# Modem.net
KiCad netlist of a schematic drawn in Altium Designer
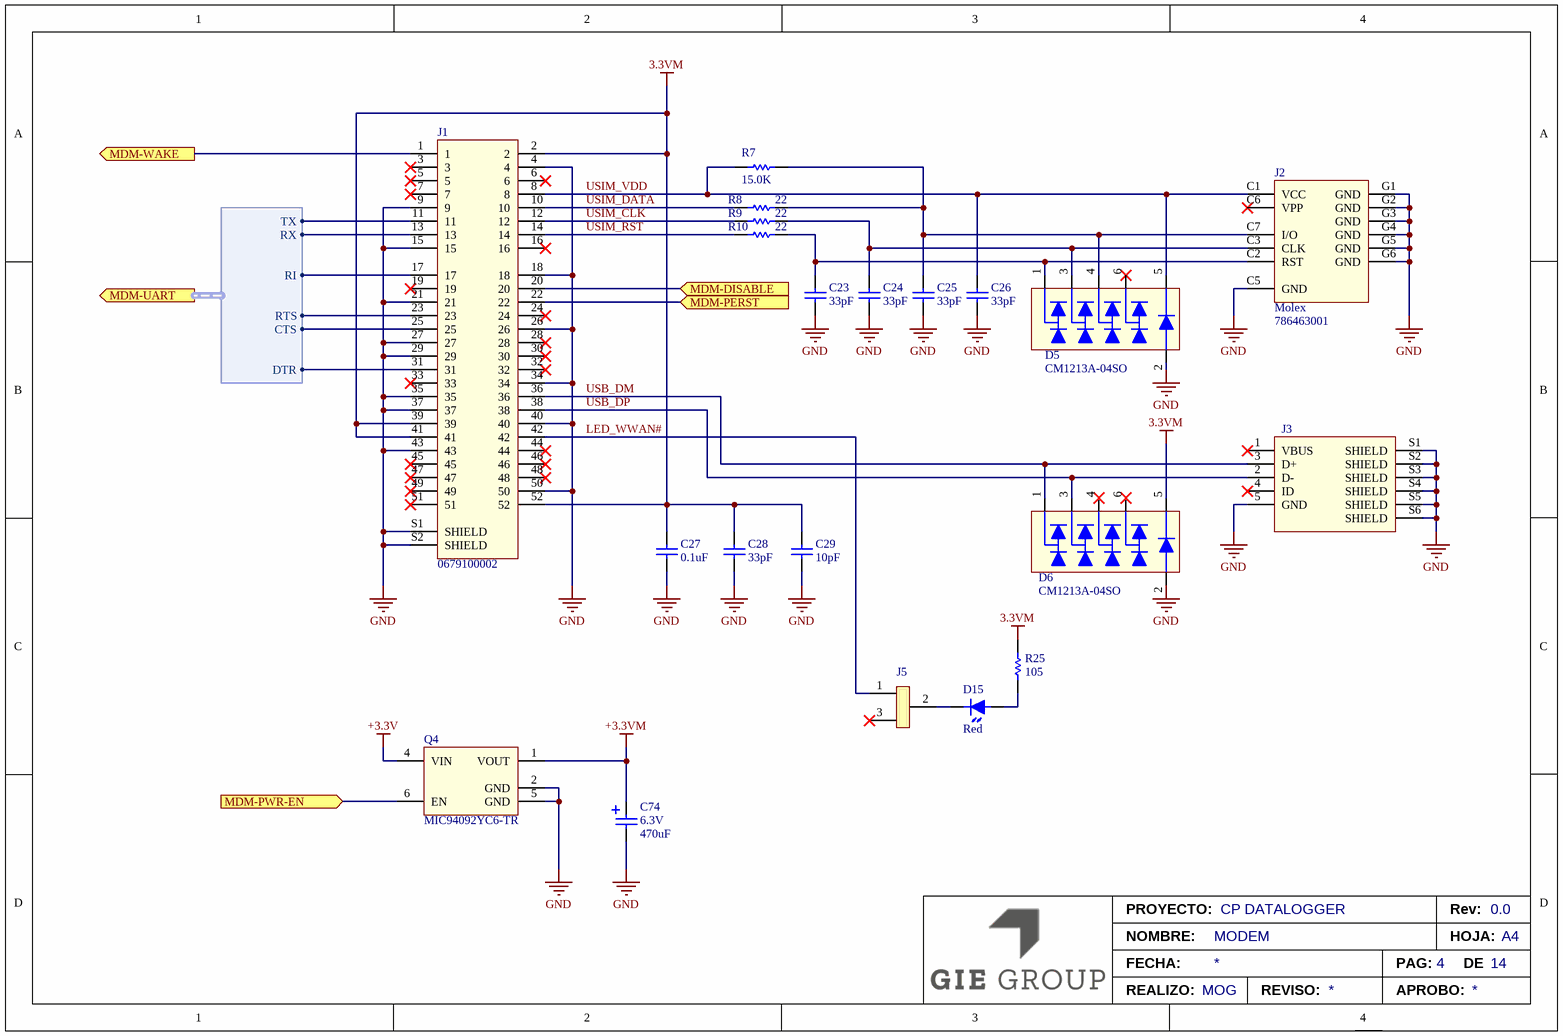
[diagram p0: Modem.SchDoc]

(export (version "E")
  (design (tool "Eeschema 10.0.6"))
  (components
    (comp (ref "C23")
      (value "33pF")
      (footprint "CAP-0603")
      (description "CAP CER 33 pF 25V C0G 0603")
      (fields (field (name "PARTNUMBER") "C0603C330F3GAC7867") (field (name "MANUFACTURER") "Kemet"))
      (libsource (lib "Kemet") (part "C0603C330F3GAC7867"))
    )
    (comp (ref "C24")
      (value "33pF")
      (footprint "CAP-0603")
      (description "CAP CER 33 pF 25V C0G 0603")
      (fields (field (name "PARTNUMBER") "C0603C330F3GAC7867") (field (name "MANUFACTURER") "Kemet"))
      (libsource (lib "Kemet") (part "C0603C330F3GAC7867"))
    )
    (comp (ref "C25")
      (value "33pF")
      (footprint "CAP-0603")
      (description "CAP CER 33 pF 25V C0G 0603")
      (fields (field (name "PARTNUMBER") "C0603C330F3GAC7867") (field (name "MANUFACTURER") "Kemet"))
      (libsource (lib "Kemet") (part "C0603C330F3GAC7867"))
    )
    (comp (ref "C26")
      (value "33pF")
      (footprint "CAP-0603")
      (description "CAP CER 33 pF 25V C0G 0603")
      (fields (field (name "PARTNUMBER") "C0603C330F3GAC7867") (field (name "MANUFACTURER") "Kemet"))
      (libsource (lib "Kemet") (part "C0603C330F3GAC7867"))
    )
    (comp (ref "C27")
      (value "0.1uF")
      (footprint "CAP-0603")
      (description "CAP CER 0.1uF 50V X7R 0603")
      (fields (field (name "PARTNUMBER") "C0603C104K5RACAUTO") (field (name "MANUFACTURER") "Kemet"))
      (libsource (lib "Kemet") (part "C0603C104K5RACAUTO"))
    )
    (comp (ref "C28")
      (value "33pF")
      (footprint "CAP-0603")
      (description "CAP CER 33 pF 25V C0G 0603")
      (fields (field (name "PARTNUMBER") "C0603C330F3GAC7867") (field (name "MANUFACTURER") "Kemet"))
      (libsource (lib "Kemet") (part "C0603C330F3GAC7867"))
    )
    (comp (ref "C29")
      (value "10pF")
      (footprint "CAP-0603")
      (description "CAP CER 10 pF 25V C0G 0603")
      (fields (field (name "PARTNUMBER") "C0603C100K3GAC7867") (field (name "MANUFACTURER") "Kemet"))
      (libsource (lib "Kemet") (part "C0603C100K3GAC7867"))
    )
    (comp (ref "C74")
      (value "470uF")
      (footprint "CAP_ALUM_SIZE_F")
      (description "CAP ALUM 470UF 20% 6.3V SMD")
      (fields
        (field (name "MANUFACTURER") "Panasonic")
        (field (name "VOLTAGE") "6.3V")
        (field (name "Comment") "EEE-FK0J471P")
      )
      (libsource (lib "Panasonic") (part "EEE-FK0J471P"))
    )
    (comp (ref "D5")
      (value "CM1213A-04SO")
      (footprint "TSSOP6")
      (description "TVS DIODE 3.3VWM 10VC 4CH SC74")
      (fields (field (name "MANUFACTURER") "OnSemiconductor") (field (name "PARTNUMBER") "CM1213A-04SO"))
      (libsource (lib "OnSemiconductors") (part "CM1213A-04SO"))
    )
    (comp (ref "D6")
      (value "CM1213A-04SO")
      (footprint "TSSOP6")
      (description "TVS DIODE 3.3VWM 10VC 4CH SC74")
      (fields (field (name "MANUFACTURER") "OnSemiconductor") (field (name "PARTNUMBER") "CM1213A-04SO"))
      (libsource (lib "OnSemiconductors") (part "CM1213A-04SO"))
    )
    (comp (ref "D15")
      (value "LTST-C170KRKT")
      (footprint "0805 - LED")
      (description "LED RED CLEAR 0805 SMD")
      (fields (field (name "MANUFACTURER") "Lite-On Inc") (field (name "COLOR") "Red"))
      (libsource (lib "LiteOn") (part "LTST-C170KRKT"))
    )
    (comp (ref "J1")
      (value "0679100002")
      (footprint "MOLEX-679100002")
      (description "Connector Mini PCI Express 52POS - Quectel modem")
      (fields (field (name "MANUFACTURER") "Molex"))
      (libsource (lib "Molex") (part "Molex 0679100002"))
    )
    (comp (ref "J2")
      (value "786463001")
      (footprint "MOLEX-786463001")
      (description "6 Position Card Connector Micro SIM Surface Mount, Right Angle Gold")
      (fields (field (name "MANUFACTURER") "Molex") (field (name "PARTNUMBER") "786463001"))
      (libsource (lib "Molex") (part "786463001"))
    )
    (comp (ref "J3")
      (value "473460001")
      (footprint "MOLEX-473460001")
      (description "USB Connectors MICRO USB B RECPT BTTM MOUNT ASSY")
      (fields (field (name "MANUFACTURER") "Molex"))
      (libsource (lib "Molex") (part "473460001"))
    )
    (comp (ref "J5")
      (value "PRPC003SAAN-RC")
      (footprint "PIN3")
      (description "CONN HEADER .100\" SNGL STR 3POS")
      (fields (field (name "MANUFACTURER") "Sullins Connector Solutions"))
      (libsource (lib "Sullins") (part "PRPC003SAAN-RC"))
    )
    (comp (ref "Q4")
      (value "MIC94092YC6-TR")
      (footprint "TSSOP6")
      (fields (field (name "MANUFACTURER") "Microchip") (field (name "PARTNUMBER") "MIC94092YC6-TR"))
      (libsource (lib "Microchip") (part "MIC94092YC6-TR"))
    )
    (comp (ref "R7")
      (value "15.0K")
      (footprint "RES-0603")
      (description "RES SMD 15.0K OHM 1% 1/10W 0603")
      (fields (field (name "TOLERANCE") "1%") (field (name "MANUFACTURER") "Yageo"))
      (libsource (lib "Yageo") (part "RC0603FR-0715KL"))
    )
    (comp (ref "R8")
      (value "22")
      (footprint "RES-0603")
      (description "RES SMD 22 OHM 1% 1/10W 0603")
      (fields (field (name "TOLERANCE") "1%") (field (name "MANUFACTURER") "Yageo"))
      (libsource (lib "Yageo") (part "RC0603FR-0722RL"))
    )
    (comp (ref "R9")
      (value "22")
      (footprint "RES-0603")
      (description "RES SMD 22 OHM 1% 1/10W 0603")
      (fields (field (name "TOLERANCE") "1%") (field (name "MANUFACTURER") "Yageo"))
      (libsource (lib "Yageo") (part "RC0603FR-0722RL"))
    )
    (comp (ref "R10")
      (value "22")
      (footprint "RES-0603")
      (description "RES SMD 22 OHM 1% 1/10W 0603")
      (fields (field (name "TOLERANCE") "1%") (field (name "MANUFACTURER") "Yageo"))
      (libsource (lib "Yageo") (part "RC0603FR-0722RL"))
    )
    (comp (ref "R25")
      (value "105")
      (footprint "RES-0603")
      (description "RES SMD 105 OHM 1% 1/8W 0805")
      (fields (field (name "TOLERANCE") "1%") (field (name "MANUFACTURER") "Yageo"))
      (libsource (lib "Yageo") (part "RC0805FR-07105RL"))
    )
  )
  (nets
    (net (code "2") (name "+3.3V") (class "Default")
      (node (ref "Q4") (pin "4") (pinfunction "VIN_4") (pintype "passive"))
    )
    (net (code "3") (name "+3.3VM") (class "Default")
      (node (ref "C74") (pin "1") (pinfunction "1_1") (pintype "passive"))
      (node (ref "Q4") (pin "1") (pinfunction "VOUT_1") (pintype "passive"))
    )
    (net (code "4") (name "/CTS") (class "Default")
      (node (ref "J1") (pin "25") (pinfunction "25_25") (pintype "passive"))
    )
    (net (code "5") (name "/DTR") (class "Default")
      (node (ref "J1") (pin "31") (pinfunction "31_31") (pintype "passive"))
    )
    (net (code "6") (name "/LED_WWAN#") (class "Default")
      (node (ref "J1") (pin "42") (pinfunction "42_42") (pintype "passive"))
      (node (ref "J5") (pin "1") (pinfunction "1_1") (pintype "passive"))
    )
    (net (code "7") (name "/MDM-DISABLE") (class "Default")
      (node (ref "J1") (pin "20") (pinfunction "20_20") (pintype "passive"))
    )
    (net (code "8") (name "/MDM-PERST") (class "Default")
      (node (ref "J1") (pin "22") (pinfunction "22_22") (pintype "passive"))
    )
    (net (code "9") (name "/MDM-PWR-EN") (class "Default")
      (node (ref "Q4") (pin "6") (pinfunction "EN_6") (pintype "passive"))
    )
    (net (code "10") (name "/MDM-WAKE") (class "Default")
      (node (ref "J1") (pin "1") (pinfunction "1_1") (pintype "passive"))
    )
    (net (code "11") (name "/RI") (class "Default")
      (node (ref "J1") (pin "17") (pinfunction "17_17") (pintype "passive"))
    )
    (net (code "12") (name "/RTS") (class "Default")
      (node (ref "J1") (pin "23") (pinfunction "23_23") (pintype "passive"))
    )
    (net (code "13") (name "/RX") (class "Default")
      (node (ref "J1") (pin "13") (pinfunction "13_13") (pintype "passive"))
    )
    (net (code "14") (name "/TX") (class "Default")
      (node (ref "J1") (pin "11") (pinfunction "11_11") (pintype "passive"))
    )
    (net (code "15") (name "/USB_DM") (class "Default")
      (node (ref "D6") (pin "1") (pinfunction "1_1") (pintype "passive"))
      (node (ref "J1") (pin "36") (pinfunction "36_36") (pintype "passive"))
      (node (ref "J3") (pin "3") (pinfunction "D+_3") (pintype "power_in"))
    )
    (net (code "16") (name "/USB_DP") (class "Default")
      (node (ref "D6") (pin "3") (pinfunction "3_3") (pintype "passive"))
      (node (ref "J1") (pin "38") (pinfunction "38_38") (pintype "passive"))
      (node (ref "J3") (pin "2") (pinfunction "D-_2") (pintype "power_in"))
    )
    (net (code "17") (name "/USIM_CLK") (class "Default")
      (node (ref "J1") (pin "12") (pinfunction "12_12") (pintype "passive"))
      (node (ref "R9") (pin "1") (pinfunction "1_1") (pintype "passive"))
    )
    (net (code "18") (name "/USIM_DATA") (class "Default")
      (node (ref "J1") (pin "10") (pinfunction "10_10") (pintype "passive"))
      (node (ref "R8") (pin "1") (pinfunction "1_1") (pintype "passive"))
    )
    (net (code "19") (name "/USIM_RST") (class "Default")
      (node (ref "J1") (pin "14") (pinfunction "14_14") (pintype "passive"))
      (node (ref "R10") (pin "1") (pinfunction "1_1") (pintype "passive"))
    )
    (net (code "20") (name "/USIM_VDD") (class "Default")
      (node (ref "C26") (pin "2") (pinfunction "2_2") (pintype "passive"))
      (node (ref "D5") (pin "5") (pinfunction "5_5") (pintype "passive"))
      (node (ref "J1") (pin "8") (pinfunction "8_8") (pintype "passive"))
      (node (ref "J2") (pin "C1") (pinfunction "VCC_C1") (pintype "power_in"))
      (node (ref "R7") (pin "1") (pinfunction "1_1") (pintype "passive"))
    )
    (net (code "22") (name "3.3VM") (class "Default")
      (node (ref "C27") (pin "2") (pinfunction "2_2") (pintype "passive"))
      (node (ref "C28") (pin "2") (pinfunction "2_2") (pintype "passive"))
      (node (ref "C29") (pin "2") (pinfunction "2_2") (pintype "passive"))
      (node (ref "D6") (pin "5") (pinfunction "5_5") (pintype "passive"))
      (node (ref "J1") (pin "2") (pinfunction "2_2") (pintype "passive"))
      (node (ref "J1") (pin "39") (pinfunction "39_39") (pintype "passive"))
      (node (ref "J1") (pin "41") (pinfunction "41_41") (pintype "passive"))
      (node (ref "J1") (pin "52") (pinfunction "52_52") (pintype "passive"))
      (node (ref "R25") (pin "2") (pinfunction "2_2") (pintype "passive"))
    )
    (net (code "23") (name "GND") (class "Default")
      (node (ref "C23") (pin "1") (pinfunction "1_1") (pintype "passive"))
      (node (ref "C24") (pin "1") (pinfunction "1_1") (pintype "passive"))
      (node (ref "C25") (pin "1") (pinfunction "1_1") (pintype "passive"))
      (node (ref "C26") (pin "1") (pinfunction "1_1") (pintype "passive"))
      (node (ref "C27") (pin "1") (pinfunction "1_1") (pintype "passive"))
      (node (ref "C28") (pin "1") (pinfunction "1_1") (pintype "passive"))
      (node (ref "C29") (pin "1") (pinfunction "1_1") (pintype "passive"))
      (node (ref "C74") (pin "2") (pinfunction "2_2") (pintype "passive"))
      (node (ref "D5") (pin "2") (pinfunction "2_2") (pintype "passive"))
      (node (ref "D6") (pin "2") (pinfunction "2_2") (pintype "passive"))
      (node (ref "J1") (pin "15") (pinfunction "15_15") (pintype "passive"))
      (node (ref "J1") (pin "18") (pinfunction "18_18") (pintype "passive"))
      (node (ref "J1") (pin "21") (pinfunction "21_21") (pintype "passive"))
      (node (ref "J1") (pin "26") (pinfunction "26_26") (pintype "passive"))
      (node (ref "J1") (pin "27") (pinfunction "27_27") (pintype "passive"))
      (node (ref "J1") (pin "29") (pinfunction "29_29") (pintype "passive"))
      (node (ref "J1") (pin "34") (pinfunction "34_34") (pintype "passive"))
      (node (ref "J1") (pin "35") (pinfunction "35_35") (pintype "passive"))
      (node (ref "J1") (pin "37") (pinfunction "37_37") (pintype "passive"))
      (node (ref "J1") (pin "4") (pinfunction "4_4") (pintype "passive"))
      (node (ref "J1") (pin "40") (pinfunction "40_40") (pintype "passive"))
      (node (ref "J1") (pin "43") (pinfunction "43_43") (pintype "passive"))
      (node (ref "J1") (pin "50") (pinfunction "50_50") (pintype "passive"))
      (node (ref "J1") (pin "9") (pinfunction "9_9") (pintype "passive"))
      (node (ref "J1") (pin "S1") (pinfunction "SHIELD_S1") (pintype "passive"))
      (node (ref "J1") (pin "S2") (pinfunction "SHIELD_S2") (pintype "passive"))
      (node (ref "J2") (pin "C5") (pinfunction "GND_C5") (pintype "power_in"))
      (node (ref "J2") (pin "G1") (pinfunction "GND_G1") (pintype "power_in"))
      (node (ref "J2") (pin "G2") (pinfunction "GND_G2") (pintype "power_in"))
      (node (ref "J2") (pin "G3") (pinfunction "GND_G3") (pintype "power_in"))
      (node (ref "J2") (pin "G4") (pinfunction "GND_G4") (pintype "power_in"))
      (node (ref "J2") (pin "G5") (pinfunction "GND_G5") (pintype "power_in"))
      (node (ref "J2") (pin "G6") (pinfunction "GND_G6") (pintype "power_in"))
      (node (ref "J3") (pin "5") (pinfunction "GND_5") (pintype "power_in"))
      (node (ref "J3") (pin "S1") (pinfunction "SHIELD_S1") (pintype "passive"))
      (node (ref "J3") (pin "S2") (pinfunction "SHIELD_S2") (pintype "passive"))
      (node (ref "J3") (pin "S3") (pinfunction "SHIELD_S3") (pintype "passive"))
      (node (ref "J3") (pin "S4") (pinfunction "SHIELD_S4") (pintype "passive"))
      (node (ref "J3") (pin "S5") (pinfunction "SHIELD_S5") (pintype "passive"))
      (node (ref "J3") (pin "S6") (pinfunction "SHIELD_S6") (pintype "passive"))
      (node (ref "Q4") (pin "2") (pinfunction "GND_2") (pintype "passive"))
      (node (ref "Q4") (pin "5") (pinfunction "GND_5") (pintype "passive"))
    )
    (net (code "24") (name "Net-(D15-A)") (class "Default")
      (node (ref "D15") (pin "1") (pinfunction "A_1") (pintype "passive"))
      (node (ref "R25") (pin "1") (pinfunction "1_1") (pintype "passive"))
    )
    (net (code "25") (name "Net-(D15-K)") (class "Default")
      (node (ref "D15") (pin "2") (pinfunction "K_2") (pintype "passive"))
      (node (ref "J5") (pin "2") (pinfunction "2_2") (pintype "passive"))
    )
    (net (code "26") (name "Net-(J2-CLK)") (class "Default")
      (node (ref "C24") (pin "2") (pinfunction "2_2") (pintype "passive"))
      (node (ref "D5") (pin "3") (pinfunction "3_3") (pintype "passive"))
      (node (ref "J2") (pin "C3") (pinfunction "CLK_C3") (pintype "power_in"))
      (node (ref "R9") (pin "2") (pinfunction "2_2") (pintype "passive"))
    )
    (net (code "27") (name "Net-(J2-I{slash}O)") (class "Default")
      (node (ref "C25") (pin "2") (pinfunction "2_2") (pintype "passive"))
      (node (ref "D5") (pin "4") (pinfunction "4_4") (pintype "passive"))
      (node (ref "J2") (pin "C7") (pinfunction "I/O_C7") (pintype "power_in"))
      (node (ref "R7") (pin "2") (pinfunction "2_2") (pintype "passive"))
      (node (ref "R8") (pin "2") (pinfunction "2_2") (pintype "passive"))
    )
    (net (code "28") (name "Net-(J2-RST)") (class "Default")
      (node (ref "C23") (pin "2") (pinfunction "2_2") (pintype "passive"))
      (node (ref "D5") (pin "1") (pinfunction "1_1") (pintype "passive"))
      (node (ref "J2") (pin "C2") (pinfunction "RST_C2") (pintype "power_in"))
      (node (ref "R10") (pin "2") (pinfunction "2_2") (pintype "passive"))
    )
    (net (code "29") (name "unconnected-(D5-Pad6)") (class "Default")
      (node (ref "D5") (pin "6") (pinfunction "6_6") (pintype "passive+no_connect"))
    )
    (net (code "30") (name "unconnected-(D6-Pad4)") (class "Default")
      (node (ref "D6") (pin "4") (pinfunction "4_4") (pintype "passive+no_connect"))
    )
    (net (code "31") (name "unconnected-(D6-Pad6)") (class "Default")
      (node (ref "D6") (pin "6") (pinfunction "6_6") (pintype "passive+no_connect"))
    )
    (net (code "32") (name "unconnected-(J1-Pad3)") (class "Default")
      (node (ref "J1") (pin "3") (pinfunction "3_3") (pintype "passive+no_connect"))
    )
    (net (code "33") (name "unconnected-(J1-Pad5)") (class "Default")
      (node (ref "J1") (pin "5") (pinfunction "5_5") (pintype "passive+no_connect"))
    )
    (net (code "34") (name "unconnected-(J1-Pad6)") (class "Default")
      (node (ref "J1") (pin "6") (pinfunction "6_6") (pintype "passive+no_connect"))
    )
    (net (code "35") (name "unconnected-(J1-Pad7)") (class "Default")
      (node (ref "J1") (pin "7") (pinfunction "7_7") (pintype "passive+no_connect"))
    )
    (net (code "36") (name "unconnected-(J1-Pad16)") (class "Default")
      (node (ref "J1") (pin "16") (pinfunction "16_16") (pintype "passive+no_connect"))
    )
    (net (code "37") (name "unconnected-(J1-Pad19)") (class "Default")
      (node (ref "J1") (pin "19") (pinfunction "19_19") (pintype "passive+no_connect"))
    )
    (net (code "38") (name "unconnected-(J1-Pad24)") (class "Default")
      (node (ref "J1") (pin "24") (pinfunction "24_24") (pintype "passive+no_connect"))
    )
    (net (code "39") (name "unconnected-(J1-Pad28)") (class "Default")
      (node (ref "J1") (pin "28") (pinfunction "28_28") (pintype "passive+no_connect"))
    )
    (net (code "40") (name "unconnected-(J1-Pad30)") (class "Default")
      (node (ref "J1") (pin "30") (pinfunction "30_30") (pintype "passive+no_connect"))
    )
    (net (code "41") (name "unconnected-(J1-Pad32)") (class "Default")
      (node (ref "J1") (pin "32") (pinfunction "32_32") (pintype "passive+no_connect"))
    )
    (net (code "42") (name "unconnected-(J1-Pad33)") (class "Default")
      (node (ref "J1") (pin "33") (pinfunction "33_33") (pintype "passive+no_connect"))
    )
    (net (code "43") (name "unconnected-(J1-Pad44)") (class "Default")
      (node (ref "J1") (pin "44") (pinfunction "44_44") (pintype "passive+no_connect"))
    )
    (net (code "44") (name "unconnected-(J1-Pad45)") (class "Default")
      (node (ref "J1") (pin "45") (pinfunction "45_45") (pintype "passive+no_connect"))
    )
    (net (code "45") (name "unconnected-(J1-Pad46)") (class "Default")
      (node (ref "J1") (pin "46") (pinfunction "46_46") (pintype "passive+no_connect"))
    )
    (net (code "46") (name "unconnected-(J1-Pad47)") (class "Default")
      (node (ref "J1") (pin "47") (pinfunction "47_47") (pintype "passive+no_connect"))
    )
    (net (code "47") (name "unconnected-(J1-Pad48)") (class "Default")
      (node (ref "J1") (pin "48") (pinfunction "48_48") (pintype "passive+no_connect"))
    )
    (net (code "48") (name "unconnected-(J1-Pad49)") (class "Default")
      (node (ref "J1") (pin "49") (pinfunction "49_49") (pintype "passive+no_connect"))
    )
    (net (code "49") (name "unconnected-(J1-Pad51)") (class "Default")
      (node (ref "J1") (pin "51") (pinfunction "51_51") (pintype "passive+no_connect"))
    )
    (net (code "50") (name "unconnected-(J2-VPP-PadC6)") (class "Default")
      (node (ref "J2") (pin "C6") (pinfunction "VPP_C6") (pintype "power_in+no_connect"))
    )
    (net (code "51") (name "unconnected-(J3-ID-Pad4)") (class "Default")
      (node (ref "J3") (pin "4") (pinfunction "ID_4") (pintype "power_in+no_connect"))
    )
    (net (code "52") (name "unconnected-(J3-VBUS-Pad1)") (class "Default")
      (node (ref "J3") (pin "1") (pinfunction "VBUS_1") (pintype "power_in+no_connect"))
    )
    (net (code "53") (name "unconnected-(J5-Pad3)") (class "Default")
      (node (ref "J5") (pin "3") (pinfunction "3_3") (pintype "passive+no_connect"))
    )
  )
)
